# Debug-unit_rev01.net
KiCad netlist of a schematic drawn in EAGLE
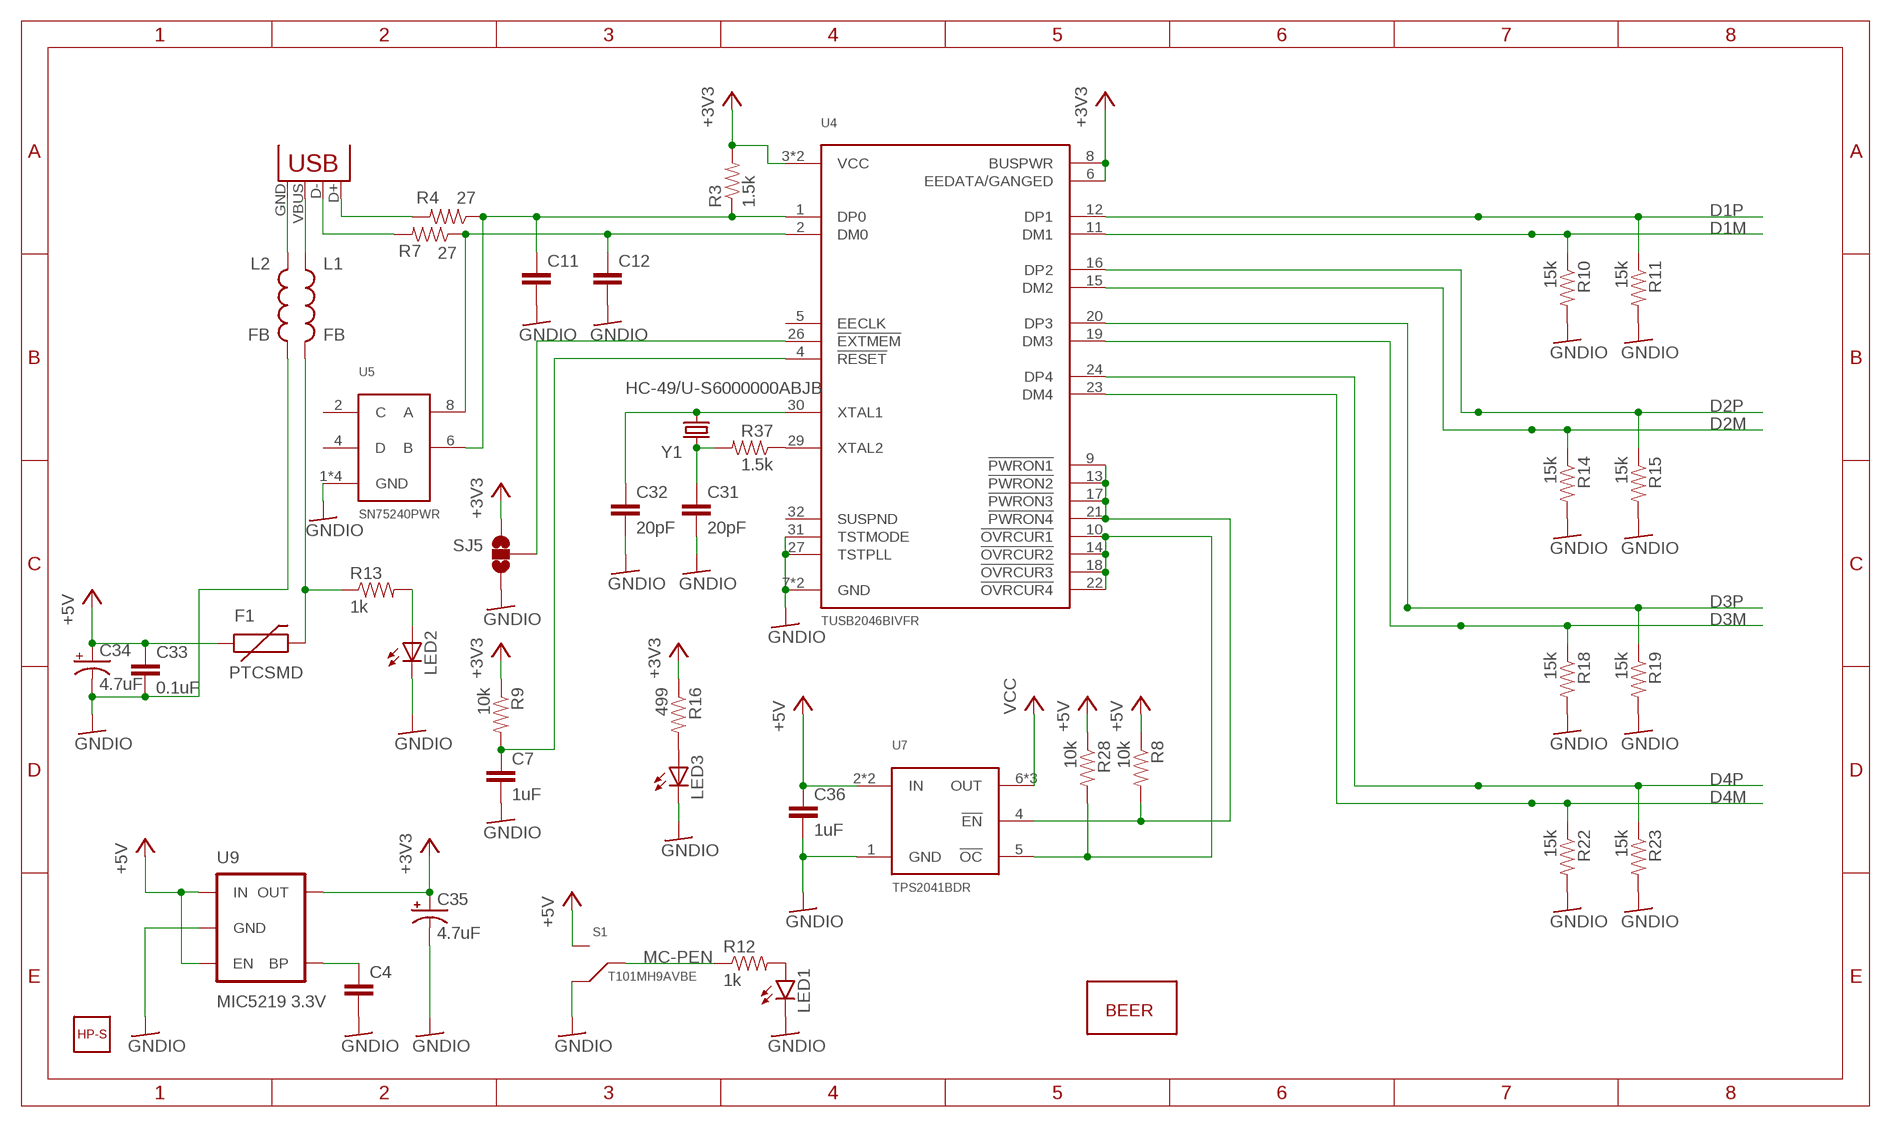
[diagram p0: schematic, sheet 1]
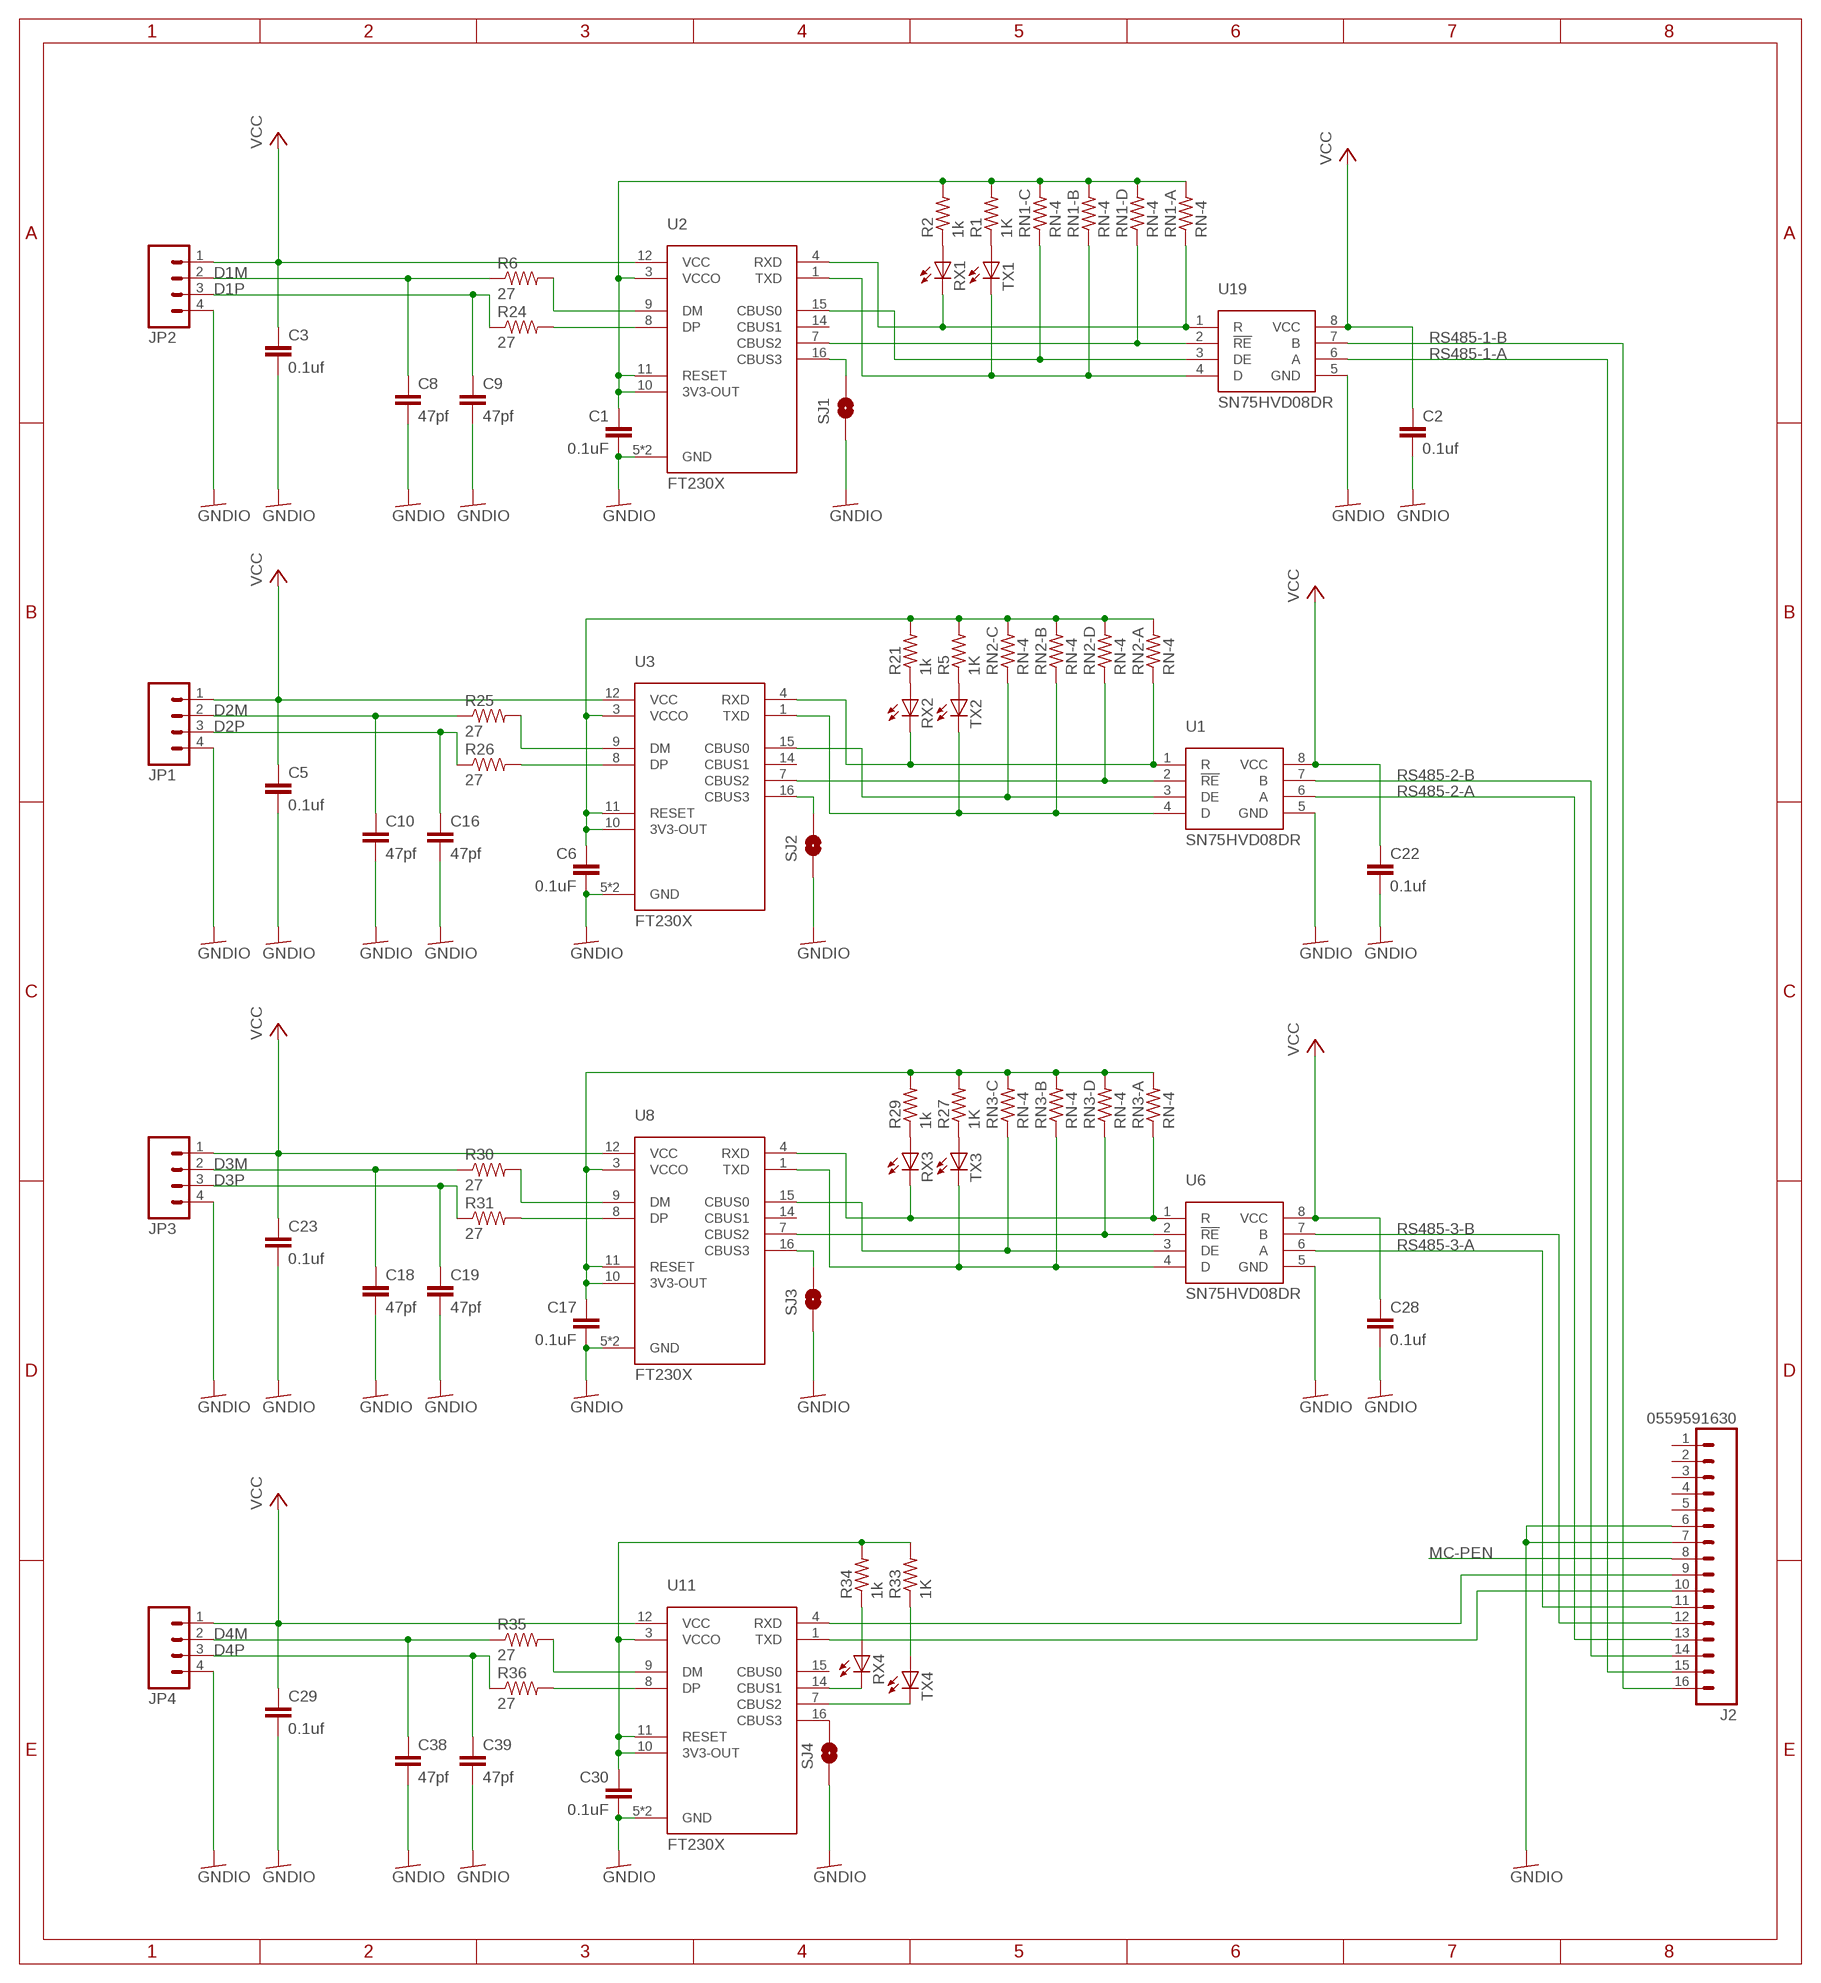
[diagram p1: schematic, sheet 2]

(export (version "E")
  (design (tool "Eeschema 10.0.6"))
  (components
    (comp (ref "C4")
      (value "CAP0805")
      (footprint "eagle-import:0805")
      (libsource (lib "eagle-import") (part "SparkFun-Passives_CAP0805"))
    )
    (comp (ref "C7")
      (value "1uF")
      (footprint "eagle-import:0805")
      (libsource (lib "eagle-import") (part "SparkFun-Passives_CAP0805"))
    )
    (comp (ref "C11")
      (value "CAP0805")
      (footprint "eagle-import:0805")
      (libsource (lib "eagle-import") (part "SparkFun-Passives_CAP0805"))
    )
    (comp (ref "C12")
      (value "CAP0805")
      (footprint "eagle-import:0805")
      (libsource (lib "eagle-import") (part "SparkFun-Passives_CAP0805"))
    )
    (comp (ref "C31")
      (value "20pF")
      (footprint "eagle-import:0805")
      (libsource (lib "eagle-import") (part "SparkFun-Passives_CAP0805"))
    )
    (comp (ref "C32")
      (value "20pF")
      (footprint "eagle-import:0805")
      (libsource (lib "eagle-import") (part "SparkFun-Passives_CAP0805"))
    )
    (comp (ref "C33")
      (value "0.1uF")
      (footprint "eagle-import:0805")
      (libsource (lib "eagle-import") (part "SparkFun-Passives_CAP0805"))
    )
    (comp (ref "C34")
      (value "4.7uF")
      (footprint "eagle-import:EIA3216")
      (libsource (lib "eagle-import") (part "CAP_POL1206"))
    )
    (comp (ref "C35")
      (value "4.7uF")
      (footprint "eagle-import:EIA3216")
      (libsource (lib "eagle-import") (part "CAP_POL1206"))
    )
    (comp (ref "C36")
      (value "1uF")
      (footprint "eagle-import:0805")
      (libsource (lib "eagle-import") (part "SparkFun-Passives_CAP0805"))
    )
    (comp (ref "F1")
      (value "PTCSMD")
      (footprint "eagle-import:PTC-1206")
      (libsource (lib "eagle-import") (part "PTCSMD"))
    )
    (comp (ref "JP9")
      (value "USB-B")
      (footprint "eagle-import:USB-B-PTH")
      (libsource (lib "eagle-import") (part "USBPTH"))
    )
    (comp (ref "L1")
      (value "FB")
      (footprint "eagle-import:0805")
      (libsource (lib "eagle-import") (part "INDUCTOR0805"))
    )
    (comp (ref "L2")
      (value "FB")
      (footprint "eagle-import:0805")
      (libsource (lib "eagle-import") (part "INDUCTOR0805"))
    )
    (comp (ref "LED1")
      (value "LED-3MM-NO_SILK")
      (footprint "eagle-import:LED3MM-NS")
      (libsource (lib "eagle-import") (part "LED-3MM-NO_SILK"))
    )
    (comp (ref "LED2")
      (value "LEDCHIP-LED0805")
      (footprint "eagle-import:CHIP-LED0805")
      (libsource (lib "eagle-import") (part "LEDCHIP-LED0805"))
    )
    (comp (ref "LED3")
      (value "LEDCHIP-LED0805")
      (footprint "eagle-import:CHIP-LED0805")
      (libsource (lib "eagle-import") (part "LEDCHIP-LED0805"))
    )
    (comp (ref "R3")
      (value "1.5k")
      (footprint "eagle-import:0805")
      (libsource (lib "eagle-import") (part "RESISTOR0805-RES"))
    )
    (comp (ref "R4")
      (value "27")
      (footprint "eagle-import:0805")
      (libsource (lib "eagle-import") (part "RESISTOR0805-RES"))
    )
    (comp (ref "R7")
      (value "27")
      (footprint "eagle-import:0805")
      (libsource (lib "eagle-import") (part "RESISTOR0805-RES"))
    )
    (comp (ref "R8")
      (value "10k")
      (footprint "eagle-import:0805")
      (libsource (lib "eagle-import") (part "RESISTOR0805-RES"))
    )
    (comp (ref "R9")
      (value "10k")
      (footprint "eagle-import:0805")
      (libsource (lib "eagle-import") (part "RESISTOR0805-RES"))
    )
    (comp (ref "R10")
      (value "15k")
      (footprint "eagle-import:0805")
      (libsource (lib "eagle-import") (part "RESISTOR0805-RES"))
    )
    (comp (ref "R11")
      (value "15k")
      (footprint "eagle-import:0805")
      (libsource (lib "eagle-import") (part "RESISTOR0805-RES"))
    )
    (comp (ref "R12")
      (value "1k")
      (footprint "eagle-import:0805")
      (libsource (lib "eagle-import") (part "RESISTOR0805-RES"))
    )
    (comp (ref "R13")
      (value "1k")
      (footprint "eagle-import:0805")
      (libsource (lib "eagle-import") (part "RESISTOR0805-RES"))
    )
    (comp (ref "R14")
      (value "15k")
      (footprint "eagle-import:0805")
      (libsource (lib "eagle-import") (part "RESISTOR0805-RES"))
    )
    (comp (ref "R15")
      (value "15k")
      (footprint "eagle-import:0805")
      (libsource (lib "eagle-import") (part "RESISTOR0805-RES"))
    )
    (comp (ref "R16")
      (value "499")
      (footprint "eagle-import:0805")
      (libsource (lib "eagle-import") (part "RESISTOR0805-RES"))
    )
    (comp (ref "R18")
      (value "15k")
      (footprint "eagle-import:0805")
      (libsource (lib "eagle-import") (part "RESISTOR0805-RES"))
    )
    (comp (ref "R19")
      (value "15k")
      (footprint "eagle-import:0805")
      (libsource (lib "eagle-import") (part "RESISTOR0805-RES"))
    )
    (comp (ref "R22")
      (value "15k")
      (footprint "eagle-import:0805")
      (libsource (lib "eagle-import") (part "RESISTOR0805-RES"))
    )
    (comp (ref "R23")
      (value "15k")
      (footprint "eagle-import:0805")
      (libsource (lib "eagle-import") (part "RESISTOR0805-RES"))
    )
    (comp (ref "R28")
      (value "10k")
      (footprint "eagle-import:0805")
      (libsource (lib "eagle-import") (part "RESISTOR0805-RES"))
    )
    (comp (ref "R37")
      (value "1.5k")
      (footprint "eagle-import:0805")
      (libsource (lib "eagle-import") (part "RESISTOR0805-RES"))
    )
    (comp (ref "S1")
      (value "T101MH9AVBE")
      (footprint "eagle-import:T101MH9AVBE")
      (libsource (lib "eagle-import") (part "T101MH9AVBE"))
    )
    (comp (ref "SJ5")
      (value "JUMPER-PAD-3-NOFULL_BOX_SILK")
      (footprint "eagle-import:PAD-JUMPER-3-NO_YES_SILK_FULL_BOX")
      (libsource (lib "eagle-import") (part "JUMPER-PAD-3-NOFULL_BOX_SILK"))
    )
    (comp (ref "U$1")
      (value "HP-3651-B")
      (footprint "eagle-import:HP-3651-B")
      (libsource (lib "eagle-import") (part "HP-3651-B"))
    )
    (comp (ref "U$3")
      (value "BEERS")
      (footprint "eagle-import:B-S")
      (libsource (lib "eagle-import") (part "BEERS"))
    )
    (comp (ref "U4")
      (value "TUSB2046BIVFR")
      (footprint "eagle-import:LQFP-32")
      (libsource (lib "eagle-import") (part "TUSB2046BIVFR"))
    )
    (comp (ref "U5")
      (value "SN75240PWR")
      (footprint "eagle-import:TSSOP-8")
      (libsource (lib "eagle-import") (part "SN75240PWR"))
    )
    (comp (ref "U7")
      (value "TPS2041BDR")
      (footprint "eagle-import:SO-8")
      (libsource (lib "eagle-import") (part "TPS2041BDR"))
    )
    (comp (ref "U9")
      (value "MIC5219 3.3V")
      (footprint "eagle-import:SOT23-5")
      (libsource (lib "eagle-import") (part "V_REG_MIC52193.3V"))
    )
    (comp (ref "Y1")
      (value "HC-49/U-S6000000ABJB")
      (footprint "eagle-import:HC49US")
      (libsource (lib "eagle-import") (part "CRYSTALHC49US"))
    )
    (comp (ref "C1")
      (value "0.1uF")
      (footprint "eagle-import:0805")
      (libsource (lib "eagle-import") (part "CAP0805"))
    )
    (comp (ref "C2")
      (value "0.1uf")
      (footprint "eagle-import:0805")
      (libsource (lib "eagle-import") (part "CAP0805"))
    )
    (comp (ref "C3")
      (value "0.1uf")
      (footprint "eagle-import:0805")
      (libsource (lib "eagle-import") (part "CAP0805"))
    )
    (comp (ref "C5")
      (value "0.1uf")
      (footprint "eagle-import:0805")
      (libsource (lib "eagle-import") (part "CAP0805"))
    )
    (comp (ref "C6")
      (value "0.1uF")
      (footprint "eagle-import:0805")
      (libsource (lib "eagle-import") (part "CAP0805"))
    )
    (comp (ref "C8")
      (value "47pf")
      (footprint "eagle-import:0805")
      (libsource (lib "eagle-import") (part "CAP0805"))
    )
    (comp (ref "C9")
      (value "47pf")
      (footprint "eagle-import:0805")
      (libsource (lib "eagle-import") (part "CAP0805"))
    )
    (comp (ref "C10")
      (value "47pf")
      (footprint "eagle-import:0805")
      (libsource (lib "eagle-import") (part "CAP0805"))
    )
    (comp (ref "C16")
      (value "47pf")
      (footprint "eagle-import:0805")
      (libsource (lib "eagle-import") (part "CAP0805"))
    )
    (comp (ref "C17")
      (value "0.1uF")
      (footprint "eagle-import:0805")
      (libsource (lib "eagle-import") (part "CAP0805"))
    )
    (comp (ref "C18")
      (value "47pf")
      (footprint "eagle-import:0805")
      (libsource (lib "eagle-import") (part "CAP0805"))
    )
    (comp (ref "C19")
      (value "47pf")
      (footprint "eagle-import:0805")
      (libsource (lib "eagle-import") (part "CAP0805"))
    )
    (comp (ref "C22")
      (value "0.1uf")
      (footprint "eagle-import:0805")
      (libsource (lib "eagle-import") (part "CAP0805"))
    )
    (comp (ref "C23")
      (value "0.1uf")
      (footprint "eagle-import:0805")
      (libsource (lib "eagle-import") (part "CAP0805"))
    )
    (comp (ref "C28")
      (value "0.1uf")
      (footprint "eagle-import:0805")
      (libsource (lib "eagle-import") (part "CAP0805"))
    )
    (comp (ref "C29")
      (value "0.1uf")
      (footprint "eagle-import:0805")
      (libsource (lib "eagle-import") (part "CAP0805"))
    )
    (comp (ref "C30")
      (value "0.1uF")
      (footprint "eagle-import:0805")
      (libsource (lib "eagle-import") (part "CAP0805"))
    )
    (comp (ref "C38")
      (value "47pf")
      (footprint "eagle-import:0805")
      (libsource (lib "eagle-import") (part "CAP0805"))
    )
    (comp (ref "C39")
      (value "47pf")
      (footprint "eagle-import:0805")
      (libsource (lib "eagle-import") (part "CAP0805"))
    )
    (comp (ref "J2")
      (value "0559591630")
      (footprint "eagle-import:0559591630")
      (libsource (lib "eagle-import") (part "0559591630"))
    )
    (comp (ref "JP1")
      (value "M04POLAR_LOCK")
      (footprint "eagle-import:MOLEX-1X4_LOCK")
      (libsource (lib "eagle-import") (part "M04POLAR_LOCK"))
    )
    (comp (ref "JP2")
      (value "M04POLAR_LOCK")
      (footprint "eagle-import:MOLEX-1X4_LOCK")
      (libsource (lib "eagle-import") (part "M04POLAR_LOCK"))
    )
    (comp (ref "JP3")
      (value "M04POLAR_LOCK")
      (footprint "eagle-import:MOLEX-1X4_LOCK")
      (libsource (lib "eagle-import") (part "M04POLAR_LOCK"))
    )
    (comp (ref "JP4")
      (value "M04POLAR_LOCK")
      (footprint "eagle-import:MOLEX-1X4_LOCK")
      (libsource (lib "eagle-import") (part "M04POLAR_LOCK"))
    )
    (comp (ref "R1")
      (value "1K")
      (footprint "eagle-import:R0805")
      (libsource (lib "eagle-import") (part "R-US_R0805"))
    )
    (comp (ref "R2")
      (value "1k")
      (footprint "eagle-import:R0805")
      (libsource (lib "eagle-import") (part "R-US_R0805"))
    )
    (comp (ref "R5")
      (value "1K")
      (footprint "eagle-import:R0805")
      (libsource (lib "eagle-import") (part "R-US_R0805"))
    )
    (comp (ref "R6")
      (value "27")
      (footprint "eagle-import:0805")
      (libsource (lib "eagle-import") (part "RESISTOR0805-RES"))
    )
    (comp (ref "R21")
      (value "1k")
      (footprint "eagle-import:R0805")
      (libsource (lib "eagle-import") (part "R-US_R0805"))
    )
    (comp (ref "R24")
      (value "27")
      (footprint "eagle-import:0805")
      (libsource (lib "eagle-import") (part "RESISTOR0805-RES"))
    )
    (comp (ref "R25")
      (value "27")
      (footprint "eagle-import:0805")
      (libsource (lib "eagle-import") (part "RESISTOR0805-RES"))
    )
    (comp (ref "R26")
      (value "27")
      (footprint "eagle-import:0805")
      (libsource (lib "eagle-import") (part "RESISTOR0805-RES"))
    )
    (comp (ref "R27")
      (value "1K")
      (footprint "eagle-import:R0805")
      (libsource (lib "eagle-import") (part "R-US_R0805"))
    )
    (comp (ref "R29")
      (value "1k")
      (footprint "eagle-import:R0805")
      (libsource (lib "eagle-import") (part "R-US_R0805"))
    )
    (comp (ref "R30")
      (value "27")
      (footprint "eagle-import:0805")
      (libsource (lib "eagle-import") (part "RESISTOR0805-RES"))
    )
    (comp (ref "R31")
      (value "27")
      (footprint "eagle-import:0805")
      (libsource (lib "eagle-import") (part "RESISTOR0805-RES"))
    )
    (comp (ref "R33")
      (value "1K")
      (footprint "eagle-import:R0805")
      (libsource (lib "eagle-import") (part "R-US_R0805"))
    )
    (comp (ref "R34")
      (value "1k")
      (footprint "eagle-import:R0805")
      (libsource (lib "eagle-import") (part "R-US_R0805"))
    )
    (comp (ref "R35")
      (value "27")
      (footprint "eagle-import:0805")
      (libsource (lib "eagle-import") (part "RESISTOR0805-RES"))
    )
    (comp (ref "R36")
      (value "27")
      (footprint "eagle-import:0805")
      (libsource (lib "eagle-import") (part "RESISTOR0805-RES"))
    )
    (comp (ref "RN1")
      (value "RN-4")
      (footprint "eagle-import:CRA06S")
      (libsource (lib "eagle-import") (part "RN-4"))
    )
    (comp (ref "RN2")
      (value "RN-4")
      (footprint "eagle-import:CRA06S")
      (libsource (lib "eagle-import") (part "RN-4"))
    )
    (comp (ref "RN3")
      (value "RN-4")
      (footprint "eagle-import:CRA06S")
      (libsource (lib "eagle-import") (part "RN-4"))
    )
    (comp (ref "RX1")
      (value "LEDCHIPLED_0805")
      (footprint "eagle-import:CHIPLED_0805")
      (libsource (lib "eagle-import") (part "LEDCHIPLED_0805"))
    )
    (comp (ref "RX2")
      (value "LEDCHIPLED_0805")
      (footprint "eagle-import:CHIPLED_0805")
      (libsource (lib "eagle-import") (part "LEDCHIPLED_0805"))
    )
    (comp (ref "RX3")
      (value "LEDCHIPLED_0805")
      (footprint "eagle-import:CHIPLED_0805")
      (libsource (lib "eagle-import") (part "LEDCHIPLED_0805"))
    )
    (comp (ref "RX4")
      (value "LEDCHIPLED_0805")
      (footprint "eagle-import:CHIPLED_0805")
      (libsource (lib "eagle-import") (part "LEDCHIPLED_0805"))
    )
    (comp (ref "SJ1")
      (value "JUMPER-PAD-2-NOYES_SILK")
      (footprint "eagle-import:PAD-JUMPER-2-NO_YES_SILK")
      (libsource (lib "eagle-import") (part "JUMPER-PAD-2-NOYES_SILK"))
    )
    (comp (ref "SJ2")
      (value "JUMPER-PAD-2-NOYES_SILK")
      (footprint "eagle-import:PAD-JUMPER-2-NO_YES_SILK")
      (libsource (lib "eagle-import") (part "JUMPER-PAD-2-NOYES_SILK"))
    )
    (comp (ref "SJ3")
      (value "JUMPER-PAD-2-NOYES_SILK")
      (footprint "eagle-import:PAD-JUMPER-2-NO_YES_SILK")
      (libsource (lib "eagle-import") (part "JUMPER-PAD-2-NOYES_SILK"))
    )
    (comp (ref "SJ4")
      (value "JUMPER-PAD-2-NOYES_SILK")
      (footprint "eagle-import:PAD-JUMPER-2-NO_YES_SILK")
      (libsource (lib "eagle-import") (part "JUMPER-PAD-2-NOYES_SILK"))
    )
    (comp (ref "TX1")
      (value "LEDCHIPLED_0805")
      (footprint "eagle-import:CHIPLED_0805")
      (libsource (lib "eagle-import") (part "LEDCHIPLED_0805"))
    )
    (comp (ref "TX2")
      (value "LEDCHIPLED_0805")
      (footprint "eagle-import:CHIPLED_0805")
      (libsource (lib "eagle-import") (part "LEDCHIPLED_0805"))
    )
    (comp (ref "TX3")
      (value "LEDCHIPLED_0805")
      (footprint "eagle-import:CHIPLED_0805")
      (libsource (lib "eagle-import") (part "LEDCHIPLED_0805"))
    )
    (comp (ref "TX4")
      (value "LEDCHIPLED_0805")
      (footprint "eagle-import:CHIPLED_0805")
      (libsource (lib "eagle-import") (part "LEDCHIPLED_0805"))
    )
    (comp (ref "U1")
      (value "SN75HVD08DR")
      (footprint "eagle-import:SO-8")
      (libsource (lib "eagle-import") (part "SN75HVD08DR"))
    )
    (comp (ref "U2")
      (value "FT230X")
      (footprint "eagle-import:SSOP-16")
      (libsource (lib "eagle-import") (part "FT230X"))
    )
    (comp (ref "U3")
      (value "FT230X")
      (footprint "eagle-import:SSOP-16")
      (libsource (lib "eagle-import") (part "FT230X"))
    )
    (comp (ref "U6")
      (value "SN75HVD08DR")
      (footprint "eagle-import:SO-8")
      (libsource (lib "eagle-import") (part "SN75HVD08DR"))
    )
    (comp (ref "U8")
      (value "FT230X")
      (footprint "eagle-import:SSOP-16")
      (libsource (lib "eagle-import") (part "FT230X"))
    )
    (comp (ref "U11")
      (value "FT230X")
      (footprint "eagle-import:SSOP-16")
      (libsource (lib "eagle-import") (part "FT230X"))
    )
    (comp (ref "U19")
      (value "SN75HVD08DR")
      (footprint "eagle-import:SO-8")
      (libsource (lib "eagle-import") (part "SN75HVD08DR"))
    )
  )
  (nets
    (net (code "1") (name "+3V3") (class "Default")
      (node (ref "C35") (pin "A") (pinfunction "+_A") (pintype "passive"))
      (node (ref "R16") (pin "1") (pinfunction "1_1") (pintype "passive"))
      (node (ref "R3") (pin "2") (pinfunction "2_2") (pintype "passive"))
      (node (ref "R9") (pin "1") (pinfunction "1_1") (pintype "passive"))
      (node (ref "SJ5") (pin "1") (pinfunction "1_1") (pintype "passive"))
      (node (ref "U4") (pin "25") (pinfunction "VCC_25") (pintype "bidirectional"))
      (node (ref "U4") (pin "3") (pinfunction "VCC_3") (pintype "bidirectional"))
      (node (ref "U4") (pin "6") (pinfunction "EEDATA/GANGED_6") (pintype "bidirectional"))
      (node (ref "U4") (pin "8") (pinfunction "BUSPWR_8") (pintype "bidirectional"))
      (node (ref "U9") (pin "5") (pinfunction "OUT_5") (pintype "passive"))
    )
    (net (code "2") (name "+5V") (class "Default")
      (node (ref "C33") (pin "1") (pinfunction "1_1") (pintype "passive"))
      (node (ref "C34") (pin "A") (pinfunction "+_A") (pintype "passive"))
      (node (ref "C36") (pin "1") (pinfunction "1_1") (pintype "passive"))
      (node (ref "F1") (pin "1") (pinfunction "1_1") (pintype "bidirectional"))
      (node (ref "R28") (pin "1") (pinfunction "1_1") (pintype "passive"))
      (node (ref "R8") (pin "1") (pinfunction "1_1") (pintype "passive"))
      (node (ref "S1") (pin "1") (pinfunction "NO_1") (pintype "bidirectional"))
      (node (ref "U7") (pin "2") (pinfunction "IN_2") (pintype "bidirectional"))
      (node (ref "U7") (pin "3") (pinfunction "IN_3") (pintype "bidirectional"))
      (node (ref "U9") (pin "1") (pinfunction "IN_1") (pintype "input"))
      (node (ref "U9") (pin "3") (pinfunction "EN_3") (pintype "input"))
    )
    (net (code "3") (name "D1M") (class "Default")
      (node (ref "C8") (pin "1") (pinfunction "1_1") (pintype "passive"))
      (node (ref "JP2") (pin "2") (pinfunction "2_2") (pintype "passive"))
      (node (ref "R10") (pin "1") (pinfunction "1_1") (pintype "passive"))
      (node (ref "R6") (pin "1") (pinfunction "1_1") (pintype "passive"))
      (node (ref "U4") (pin "11") (pinfunction "DM1_11") (pintype "bidirectional"))
    )
    (net (code "4") (name "D1P") (class "Default")
      (node (ref "C9") (pin "1") (pinfunction "1_1") (pintype "passive"))
      (node (ref "JP2") (pin "3") (pinfunction "3_3") (pintype "passive"))
      (node (ref "R11") (pin "1") (pinfunction "1_1") (pintype "passive"))
      (node (ref "R24") (pin "1") (pinfunction "1_1") (pintype "passive"))
      (node (ref "U4") (pin "12") (pinfunction "DP1_12") (pintype "bidirectional"))
    )
    (net (code "5") (name "D2M") (class "Default")
      (node (ref "C10") (pin "1") (pinfunction "1_1") (pintype "passive"))
      (node (ref "JP1") (pin "2") (pinfunction "2_2") (pintype "passive"))
      (node (ref "R14") (pin "1") (pinfunction "1_1") (pintype "passive"))
      (node (ref "R25") (pin "1") (pinfunction "1_1") (pintype "passive"))
      (node (ref "U4") (pin "15") (pinfunction "DM2_15") (pintype "bidirectional"))
    )
    (net (code "6") (name "D2P") (class "Default")
      (node (ref "C16") (pin "1") (pinfunction "1_1") (pintype "passive"))
      (node (ref "JP1") (pin "3") (pinfunction "3_3") (pintype "passive"))
      (node (ref "R15") (pin "1") (pinfunction "1_1") (pintype "passive"))
      (node (ref "R26") (pin "1") (pinfunction "1_1") (pintype "passive"))
      (node (ref "U4") (pin "16") (pinfunction "DP2_16") (pintype "bidirectional"))
    )
    (net (code "7") (name "D3M") (class "Default")
      (node (ref "C18") (pin "1") (pinfunction "1_1") (pintype "passive"))
      (node (ref "JP3") (pin "2") (pinfunction "2_2") (pintype "passive"))
      (node (ref "R18") (pin "1") (pinfunction "1_1") (pintype "passive"))
      (node (ref "R30") (pin "1") (pinfunction "1_1") (pintype "passive"))
      (node (ref "U4") (pin "19") (pinfunction "DM3_19") (pintype "bidirectional"))
    )
    (net (code "8") (name "D3P") (class "Default")
      (node (ref "C19") (pin "1") (pinfunction "1_1") (pintype "passive"))
      (node (ref "JP3") (pin "3") (pinfunction "3_3") (pintype "passive"))
      (node (ref "R19") (pin "1") (pinfunction "1_1") (pintype "passive"))
      (node (ref "R31") (pin "1") (pinfunction "1_1") (pintype "passive"))
      (node (ref "U4") (pin "20") (pinfunction "DP3_20") (pintype "bidirectional"))
    )
    (net (code "9") (name "D4M") (class "Default")
      (node (ref "C38") (pin "1") (pinfunction "1_1") (pintype "passive"))
      (node (ref "JP4") (pin "2") (pinfunction "2_2") (pintype "passive"))
      (node (ref "R22") (pin "1") (pinfunction "1_1") (pintype "passive"))
      (node (ref "R35") (pin "1") (pinfunction "1_1") (pintype "passive"))
      (node (ref "U4") (pin "23") (pinfunction "DM4_23") (pintype "bidirectional"))
    )
    (net (code "10") (name "D4P") (class "Default")
      (node (ref "C39") (pin "1") (pinfunction "1_1") (pintype "passive"))
      (node (ref "JP4") (pin "3") (pinfunction "3_3") (pintype "passive"))
      (node (ref "R23") (pin "1") (pinfunction "1_1") (pintype "passive"))
      (node (ref "R36") (pin "1") (pinfunction "1_1") (pintype "passive"))
      (node (ref "U4") (pin "24") (pinfunction "DP4_24") (pintype "bidirectional"))
    )
    (net (code "11") (name "GNDIO") (class "Default")
      (node (ref "C1") (pin "2") (pinfunction "2_2") (pintype "passive"))
      (node (ref "C10") (pin "2") (pinfunction "2_2") (pintype "passive"))
      (node (ref "C11") (pin "2") (pinfunction "2_2") (pintype "passive"))
      (node (ref "C12") (pin "2") (pinfunction "2_2") (pintype "passive"))
      (node (ref "C16") (pin "2") (pinfunction "2_2") (pintype "passive"))
      (node (ref "C17") (pin "2") (pinfunction "2_2") (pintype "passive"))
      (node (ref "C18") (pin "2") (pinfunction "2_2") (pintype "passive"))
      (node (ref "C19") (pin "2") (pinfunction "2_2") (pintype "passive"))
      (node (ref "C2") (pin "2") (pinfunction "2_2") (pintype "passive"))
      (node (ref "C22") (pin "2") (pinfunction "2_2") (pintype "passive"))
      (node (ref "C23") (pin "2") (pinfunction "2_2") (pintype "passive"))
      (node (ref "C28") (pin "2") (pinfunction "2_2") (pintype "passive"))
      (node (ref "C29") (pin "2") (pinfunction "2_2") (pintype "passive"))
      (node (ref "C3") (pin "2") (pinfunction "2_2") (pintype "passive"))
      (node (ref "C30") (pin "2") (pinfunction "2_2") (pintype "passive"))
      (node (ref "C31") (pin "2") (pinfunction "2_2") (pintype "passive"))
      (node (ref "C32") (pin "2") (pinfunction "2_2") (pintype "passive"))
      (node (ref "C33") (pin "2") (pinfunction "2_2") (pintype "passive"))
      (node (ref "C34") (pin "C") (pinfunction "-_C") (pintype "passive"))
      (node (ref "C35") (pin "C") (pinfunction "-_C") (pintype "passive"))
      (node (ref "C36") (pin "2") (pinfunction "2_2") (pintype "passive"))
      (node (ref "C38") (pin "2") (pinfunction "2_2") (pintype "passive"))
      (node (ref "C39") (pin "2") (pinfunction "2_2") (pintype "passive"))
      (node (ref "C4") (pin "2") (pinfunction "2_2") (pintype "passive"))
      (node (ref "C5") (pin "2") (pinfunction "2_2") (pintype "passive"))
      (node (ref "C6") (pin "2") (pinfunction "2_2") (pintype "passive"))
      (node (ref "C7") (pin "2") (pinfunction "2_2") (pintype "passive"))
      (node (ref "C8") (pin "2") (pinfunction "2_2") (pintype "passive"))
      (node (ref "C9") (pin "2") (pinfunction "2_2") (pintype "passive"))
      (node (ref "J2") (pin "6") (pinfunction "6_6") (pintype "passive"))
      (node (ref "J2") (pin "7") (pinfunction "7_7") (pintype "passive"))
      (node (ref "JP1") (pin "4") (pinfunction "4_4") (pintype "passive"))
      (node (ref "JP2") (pin "4") (pinfunction "4_4") (pintype "passive"))
      (node (ref "JP3") (pin "4") (pinfunction "4_4") (pintype "passive"))
      (node (ref "JP4") (pin "4") (pinfunction "4_4") (pintype "passive"))
      (node (ref "L2") (pin "2") (pinfunction "2_2") (pintype "passive"))
      (node (ref "LED1") (pin "K") (pinfunction "C_K") (pintype "passive"))
      (node (ref "LED2") (pin "C") (pinfunction "C_C") (pintype "passive"))
      (node (ref "LED3") (pin "C") (pinfunction "C_C") (pintype "passive"))
      (node (ref "R10") (pin "2") (pinfunction "2_2") (pintype "passive"))
      (node (ref "R11") (pin "2") (pinfunction "2_2") (pintype "passive"))
      (node (ref "R14") (pin "2") (pinfunction "2_2") (pintype "passive"))
      (node (ref "R15") (pin "2") (pinfunction "2_2") (pintype "passive"))
      (node (ref "R18") (pin "2") (pinfunction "2_2") (pintype "passive"))
      (node (ref "R19") (pin "2") (pinfunction "2_2") (pintype "passive"))
      (node (ref "R22") (pin "2") (pinfunction "2_2") (pintype "passive"))
      (node (ref "R23") (pin "2") (pinfunction "2_2") (pintype "passive"))
      (node (ref "S1") (pin "3") (pinfunction "NC_3") (pintype "bidirectional"))
      (node (ref "SJ1") (pin "1") (pinfunction "1_1") (pintype "passive"))
      (node (ref "SJ2") (pin "1") (pinfunction "1_1") (pintype "passive"))
      (node (ref "SJ3") (pin "1") (pinfunction "1_1") (pintype "passive"))
      (node (ref "SJ4") (pin "1") (pinfunction "1_1") (pintype "passive"))
      (node (ref "SJ5") (pin "3") (pinfunction "3_3") (pintype "passive"))
      (node (ref "U1") (pin "5") (pinfunction "GND_5") (pintype "bidirectional"))
      (node (ref "U11") (pin "13") (pinfunction "GND_13") (pintype "bidirectional"))
      (node (ref "U11") (pin "5") (pinfunction "GND_5") (pintype "bidirectional"))
      (node (ref "U19") (pin "5") (pinfunction "GND_5") (pintype "bidirectional"))
      (node (ref "U2") (pin "13") (pinfunction "GND_13") (pintype "bidirectional"))
      (node (ref "U2") (pin "5") (pinfunction "GND_5") (pintype "bidirectional"))
      (node (ref "U3") (pin "13") (pinfunction "GND_13") (pintype "bidirectional"))
      (node (ref "U3") (pin "5") (pinfunction "GND_5") (pintype "bidirectional"))
      (node (ref "U4") (pin "27") (pinfunction "TSTPLL_27") (pintype "bidirectional"))
      (node (ref "U4") (pin "28") (pinfunction "GND_28") (pintype "bidirectional"))
      (node (ref "U4") (pin "31") (pinfunction "TSTMODE_31") (pintype "bidirectional"))
      (node (ref "U4") (pin "7") (pinfunction "GND_7") (pintype "bidirectional"))
      (node (ref "U5") (pin "1") (pinfunction "GND_1") (pintype "bidirectional"))
      (node (ref "U5") (pin "3") (pinfunction "GND_3") (pintype "bidirectional"))
      (node (ref "U5") (pin "5") (pinfunction "GND_5") (pintype "bidirectional"))
      (node (ref "U5") (pin "7") (pinfunction "GND_7") (pintype "bidirectional"))
      (node (ref "U6") (pin "5") (pinfunction "GND_5") (pintype "bidirectional"))
      (node (ref "U7") (pin "1") (pinfunction "GND_1") (pintype "bidirectional"))
      (node (ref "U8") (pin "13") (pinfunction "GND_13") (pintype "bidirectional"))
      (node (ref "U8") (pin "5") (pinfunction "GND_5") (pintype "bidirectional"))
      (node (ref "U9") (pin "2") (pinfunction "GND_2") (pintype "input"))
    )
    (net (code "12") (name "MC-PEN") (class "Default")
      (node (ref "J2") (pin "8") (pinfunction "8_8") (pintype "passive"))
      (node (ref "R12") (pin "1") (pinfunction "1_1") (pintype "passive"))
      (node (ref "S1") (pin "2") (pinfunction "C_2") (pintype "bidirectional"))
    )
    (net (code "13") (name "Net-(C31-Pad1)") (class "Default")
      (node (ref "C31") (pin "1") (pinfunction "1_1") (pintype "passive"))
      (node (ref "R37") (pin "2") (pinfunction "2_2") (pintype "passive"))
      (node (ref "Y1") (pin "2") (pinfunction "2_2") (pintype "passive"))
    )
    (net (code "14") (name "Net-(F1-Pad2)") (class "Default")
      (node (ref "F1") (pin "2") (pinfunction "2_2") (pintype "bidirectional"))
      (node (ref "L1") (pin "2") (pinfunction "2_2") (pintype "passive"))
      (node (ref "R13") (pin "1") (pinfunction "1_1") (pintype "passive"))
    )
    (net (code "15") (name "Net-(JP9-PadD+)") (class "Default")
      (node (ref "JP9") (pin "D+") (pinfunction "D+_D+") (pintype "bidirectional"))
      (node (ref "R4") (pin "2") (pinfunction "2_2") (pintype "passive"))
    )
    (net (code "16") (name "Net-(JP9-PadD-)") (class "Default")
      (node (ref "JP9") (pin "D-") (pinfunction "D-_D-") (pintype "bidirectional"))
      (node (ref "R7") (pin "2") (pinfunction "2_2") (pintype "passive"))
    )
    (net (code "17") (name "Net-(JP9-PadGND)") (class "Default")
      (node (ref "JP9") (pin "GND") (pinfunction "GND_GND") (pintype "bidirectional"))
      (node (ref "L2") (pin "1") (pinfunction "1_1") (pintype "passive"))
    )
    (net (code "18") (name "Net-(JP9-PadVBUS)") (class "Default")
      (node (ref "JP9") (pin "VBUS") (pinfunction "VBUS_VBUS") (pintype "bidirectional"))
      (node (ref "L1") (pin "1") (pinfunction "1_1") (pintype "passive"))
    )
    (net (code "19") (name "Net-(LED1-PadA)") (class "Default")
      (node (ref "LED1") (pin "A") (pinfunction "A_A") (pintype "passive"))
      (node (ref "R12") (pin "2") (pinfunction "2_2") (pintype "passive"))
    )
    (net (code "20") (name "Net-(LED2-PadA)") (class "Default")
      (node (ref "LED2") (pin "A") (pinfunction "A_A") (pintype "passive"))
      (node (ref "R13") (pin "2") (pinfunction "2_2") (pintype "passive"))
    )
    (net (code "21") (name "Net-(LED3-PadA)") (class "Default")
      (node (ref "LED3") (pin "A") (pinfunction "A_A") (pintype "passive"))
      (node (ref "R16") (pin "2") (pinfunction "2_2") (pintype "passive"))
    )
    (net (code "22") (name "Net-(R1-Pad1)") (class "Default")
      (node (ref "R1") (pin "1") (pinfunction "1_1") (pintype "passive"))
      (node (ref "TX1") (pin "A") (pinfunction "A_A") (pintype "passive"))
    )
    (net (code "23") (name "Net-(R2-Pad1)") (class "Default")
      (node (ref "R2") (pin "1") (pinfunction "1_1") (pintype "passive"))
      (node (ref "RX1") (pin "A") (pinfunction "A_A") (pintype "passive"))
    )
    (net (code "24") (name "Net-(R5-Pad1)") (class "Default")
      (node (ref "R5") (pin "1") (pinfunction "1_1") (pintype "passive"))
      (node (ref "TX2") (pin "A") (pinfunction "A_A") (pintype "passive"))
    )
    (net (code "25") (name "Net-(R21-Pad1)") (class "Default")
      (node (ref "R21") (pin "1") (pinfunction "1_1") (pintype "passive"))
      (node (ref "RX2") (pin "A") (pinfunction "A_A") (pintype "passive"))
    )
    (net (code "26") (name "Net-(R27-Pad1)") (class "Default")
      (node (ref "R27") (pin "1") (pinfunction "1_1") (pintype "passive"))
      (node (ref "TX3") (pin "A") (pinfunction "A_A") (pintype "passive"))
    )
    (net (code "27") (name "Net-(R29-Pad1)") (class "Default")
      (node (ref "R29") (pin "1") (pinfunction "1_1") (pintype "passive"))
      (node (ref "RX3") (pin "A") (pinfunction "A_A") (pintype "passive"))
    )
    (net (code "28") (name "Net-(R33-Pad1)") (class "Default")
      (node (ref "R33") (pin "1") (pinfunction "1_1") (pintype "passive"))
      (node (ref "TX4") (pin "A") (pinfunction "A_A") (pintype "passive"))
    )
    (net (code "29") (name "Net-(R34-Pad1)") (class "Default")
      (node (ref "R34") (pin "1") (pinfunction "1_1") (pintype "passive"))
      (node (ref "RX4") (pin "A") (pinfunction "A_A") (pintype "passive"))
    )
    (net (code "30") (name "Net-(RN1A-2)") (class "Default")
      (node (ref "C1") (pin "1") (pinfunction "1_1") (pintype "passive"))
      (node (ref "R1") (pin "2") (pinfunction "2_2") (pintype "passive"))
      (node (ref "R2") (pin "2") (pinfunction "2_2") (pintype "passive"))
      (node (ref "RN1") (pin "5") (pinfunction "2_5") (pintype "passive"))
      (node (ref "RN1") (pin "6") (pinfunction "2_6") (pintype "passive"))
      (node (ref "RN1") (pin "7") (pinfunction "2_7") (pintype "passive"))
      (node (ref "RN1") (pin "8") (pinfunction "2_8") (pintype "passive"))
      (node (ref "U2") (pin "10") (pinfunction "3V3-OUT_10") (pintype "bidirectional"))
      (node (ref "U2") (pin "11") (pinfunction "RESET_11") (pintype "bidirectional"))
      (node (ref "U2") (pin "3") (pinfunction "VCCO_3") (pintype "bidirectional"))
    )
    (net (code "31") (name "Net-(RN1B-1)") (class "Default")
      (node (ref "RN1") (pin "2") (pinfunction "1_2") (pintype "passive"))
      (node (ref "TX1") (pin "C") (pinfunction "C_C") (pintype "passive"))
      (node (ref "U19") (pin "4") (pinfunction "D_4") (pintype "bidirectional"))
      (node (ref "U2") (pin "1") (pinfunction "TXD_1") (pintype "bidirectional"))
    )
    (net (code "32") (name "Net-(RN1C-1)") (class "Default")
      (node (ref "RN1") (pin "3") (pinfunction "1_3") (pintype "passive"))
      (node (ref "U19") (pin "3") (pinfunction "DE_3") (pintype "bidirectional"))
      (node (ref "U2") (pin "15") (pinfunction "CBUS0_15") (pintype "bidirectional"))
    )
    (net (code "33") (name "Net-(RN1D-1)") (class "Default")
      (node (ref "RN1") (pin "4") (pinfunction "1_4") (pintype "passive"))
      (node (ref "U19") (pin "2") (pinfunction "~{RE}_2") (pintype "bidirectional"))
      (node (ref "U2") (pin "7") (pinfunction "CBUS2_7") (pintype "bidirectional"))
    )
    (net (code "34") (name "Net-(RN2A-2)") (class "Default")
      (node (ref "C6") (pin "1") (pinfunction "1_1") (pintype "passive"))
      (node (ref "R21") (pin "2") (pinfunction "2_2") (pintype "passive"))
      (node (ref "R5") (pin "2") (pinfunction "2_2") (pintype "passive"))
      (node (ref "RN2") (pin "5") (pinfunction "2_5") (pintype "passive"))
      (node (ref "RN2") (pin "6") (pinfunction "2_6") (pintype "passive"))
      (node (ref "RN2") (pin "7") (pinfunction "2_7") (pintype "passive"))
      (node (ref "RN2") (pin "8") (pinfunction "2_8") (pintype "passive"))
      (node (ref "U3") (pin "10") (pinfunction "3V3-OUT_10") (pintype "bidirectional"))
      (node (ref "U3") (pin "11") (pinfunction "RESET_11") (pintype "bidirectional"))
      (node (ref "U3") (pin "3") (pinfunction "VCCO_3") (pintype "bidirectional"))
    )
    (net (code "35") (name "Net-(RN2B-1)") (class "Default")
      (node (ref "RN2") (pin "2") (pinfunction "1_2") (pintype "passive"))
      (node (ref "TX2") (pin "C") (pinfunction "C_C") (pintype "passive"))
      (node (ref "U1") (pin "4") (pinfunction "D_4") (pintype "bidirectional"))
      (node (ref "U3") (pin "1") (pinfunction "TXD_1") (pintype "bidirectional"))
    )
    (net (code "36") (name "Net-(RN2C-1)") (class "Default")
      (node (ref "RN2") (pin "3") (pinfunction "1_3") (pintype "passive"))
      (node (ref "U1") (pin "3") (pinfunction "DE_3") (pintype "bidirectional"))
      (node (ref "U3") (pin "15") (pinfunction "CBUS0_15") (pintype "bidirectional"))
    )
    (net (code "37") (name "Net-(RN2D-1)") (class "Default")
      (node (ref "RN2") (pin "4") (pinfunction "1_4") (pintype "passive"))
      (node (ref "U1") (pin "2") (pinfunction "~{RE}_2") (pintype "bidirectional"))
      (node (ref "U3") (pin "7") (pinfunction "CBUS2_7") (pintype "bidirectional"))
    )
    (net (code "38") (name "Net-(RN3A-2)") (class "Default")
      (node (ref "C17") (pin "1") (pinfunction "1_1") (pintype "passive"))
      (node (ref "R27") (pin "2") (pinfunction "2_2") (pintype "passive"))
      (node (ref "R29") (pin "2") (pinfunction "2_2") (pintype "passive"))
      (node (ref "RN3") (pin "5") (pinfunction "2_5") (pintype "passive"))
      (node (ref "RN3") (pin "6") (pinfunction "2_6") (pintype "passive"))
      (node (ref "RN3") (pin "7") (pinfunction "2_7") (pintype "passive"))
      (node (ref "RN3") (pin "8") (pinfunction "2_8") (pintype "passive"))
      (node (ref "U8") (pin "10") (pinfunction "3V3-OUT_10") (pintype "bidirectional"))
      (node (ref "U8") (pin "11") (pinfunction "RESET_11") (pintype "bidirectional"))
      (node (ref "U8") (pin "3") (pinfunction "VCCO_3") (pintype "bidirectional"))
    )
    (net (code "39") (name "Net-(RN3B-1)") (class "Default")
      (node (ref "RN3") (pin "2") (pinfunction "1_2") (pintype "passive"))
      (node (ref "TX3") (pin "C") (pinfunction "C_C") (pintype "passive"))
      (node (ref "U6") (pin "4") (pinfunction "D_4") (pintype "bidirectional"))
      (node (ref "U8") (pin "1") (pinfunction "TXD_1") (pintype "bidirectional"))
    )
    (net (code "40") (name "Net-(RN3C-1)") (class "Default")
      (node (ref "RN3") (pin "3") (pinfunction "1_3") (pintype "passive"))
      (node (ref "U6") (pin "3") (pinfunction "DE_3") (pintype "bidirectional"))
      (node (ref "U8") (pin "15") (pinfunction "CBUS0_15") (pintype "bidirectional"))
    )
    (net (code "41") (name "Net-(RN3D-1)") (class "Default")
      (node (ref "RN3") (pin "4") (pinfunction "1_4") (pintype "passive"))
      (node (ref "U6") (pin "2") (pinfunction "~{RE}_2") (pintype "bidirectional"))
      (node (ref "U8") (pin "7") (pinfunction "CBUS2_7") (pintype "bidirectional"))
    )
    (net (code "42") (name "Net-(U1-R)") (class "Default")
      (node (ref "RN2") (pin "1") (pinfunction "1_1") (pintype "passive"))
      (node (ref "RX2") (pin "C") (pinfunction "C_C") (pintype "passive"))
      (node (ref "U1") (pin "1") (pinfunction "R_1") (pintype "bidirectional"))
      (node (ref "U3") (pin "4") (pinfunction "RXD_4") (pintype "bidirectional"))
    )
    (net (code "43") (name "Net-(U2-CBUS3)") (class "Default")
      (node (ref "SJ1") (pin "2") (pinfunction "2_2") (pintype "passive"))
      (node (ref "U2") (pin "16") (pinfunction "CBUS3_16") (pintype "bidirectional"))
    )
    (net (code "44") (name "Net-(U2-DM)") (class "Default")
      (node (ref "R6") (pin "2") (pinfunction "2_2") (pintype "passive"))
      (node (ref "U2") (pin "9") (pinfunction "DM_9") (pintype "bidirectional"))
    )
    (net (code "45") (name "Net-(U2-DP)") (class "Default")
      (node (ref "R24") (pin "2") (pinfunction "2_2") (pintype "passive"))
      (node (ref "U2") (pin "8") (pinfunction "DP_8") (pintype "bidirectional"))
    )
    (net (code "46") (name "Net-(U3-CBUS3)") (class "Default")
      (node (ref "SJ2") (pin "2") (pinfunction "2_2") (pintype "passive"))
      (node (ref "U3") (pin "16") (pinfunction "CBUS3_16") (pintype "bidirectional"))
    )
    (net (code "47") (name "Net-(U3-DM)") (class "Default")
      (node (ref "R25") (pin "2") (pinfunction "2_2") (pintype "passive"))
      (node (ref "U3") (pin "9") (pinfunction "DM_9") (pintype "bidirectional"))
    )
    (net (code "48") (name "Net-(U3-DP)") (class "Default")
      (node (ref "R26") (pin "2") (pinfunction "2_2") (pintype "passive"))
      (node (ref "U3") (pin "8") (pinfunction "DP_8") (pintype "bidirectional"))
    )
    (net (code "49") (name "Net-(U4-DM0)") (class "Default")
      (node (ref "C12") (pin "1") (pinfunction "1_1") (pintype "passive"))
      (node (ref "R7") (pin "1") (pinfunction "1_1") (pintype "passive"))
      (node (ref "U4") (pin "2") (pinfunction "DM0_2") (pintype "bidirectional"))
      (node (ref "U5") (pin "8") (pinfunction "A_8") (pintype "bidirectional"))
    )
    (net (code "50") (name "Net-(U4-DP0)") (class "Default")
      (node (ref "C11") (pin "1") (pinfunction "1_1") (pintype "passive"))
      (node (ref "R3") (pin "1") (pinfunction "1_1") (pintype "passive"))
      (node (ref "R4") (pin "1") (pinfunction "1_1") (pintype "passive"))
      (node (ref "U4") (pin "1") (pinfunction "DP0_1") (pintype "bidirectional"))
      (node (ref "U5") (pin "6") (pinfunction "B_6") (pintype "bidirectional"))
    )
    (net (code "51") (name "Net-(U4-XTAL1)") (class "Default")
      (node (ref "C32") (pin "1") (pinfunction "1_1") (pintype "passive"))
      (node (ref "U4") (pin "30") (pinfunction "XTAL1_30") (pintype "bidirectional"))
      (node (ref "Y1") (pin "1") (pinfunction "1_1") (pintype "passive"))
    )
    (net (code "52") (name "Net-(U4-XTAL2)") (class "Default")
      (node (ref "R37") (pin "1") (pinfunction "1_1") (pintype "passive"))
      (node (ref "U4") (pin "29") (pinfunction "XTAL2_29") (pintype "bidirectional"))
    )
    (net (code "53") (name "Net-(U4-~{EXTMEM})") (class "Default")
      (node (ref "SJ5") (pin "2") (pinfunction "2_2") (pintype "passive"))
      (node (ref "U4") (pin "26") (pinfunction "~{EXTMEM}_26") (pintype "bidirectional"))
    )
    (net (code "54") (name "Net-(U4-~{OVRCUR1})") (class "Default")
      (node (ref "R28") (pin "2") (pinfunction "2_2") (pintype "passive"))
      (node (ref "U4") (pin "10") (pinfunction "~{OVRCUR1}_10") (pintype "bidirectional"))
      (node (ref "U4") (pin "14") (pinfunction "~{OVRCUR2}_14") (pintype "bidirectional"))
      (node (ref "U4") (pin "18") (pinfunction "~{OVRCUR3}_18") (pintype "bidirectional"))
      (node (ref "U4") (pin "22") (pinfunction "~{OVRCUR4}_22") (pintype "bidirectional"))
      (node (ref "U7") (pin "5") (pinfunction "~{OC}_5") (pintype "bidirectional"))
    )
    (net (code "55") (name "Net-(U4-~{PWRON1})") (class "Default")
      (node (ref "R8") (pin "2") (pinfunction "2_2") (pintype "passive"))
      (node (ref "U4") (pin "13") (pinfunction "~{PWRON2}_13") (pintype "bidirectional"))
      (node (ref "U4") (pin "17") (pinfunction "~{PWRON3}_17") (pintype "bidirectional"))
      (node (ref "U4") (pin "21") (pinfunction "~{PWRON4}_21") (pintype "bidirectional"))
      (node (ref "U4") (pin "9") (pinfunction "~{PWRON1}_9") (pintype "bidirectional"))
      (node (ref "U7") (pin "4") (pinfunction "~{EN}_4") (pintype "bidirectional"))
    )
    (net (code "56") (name "Net-(U4-~{RESET})") (class "Default")
      (node (ref "C7") (pin "1") (pinfunction "1_1") (pintype "passive"))
      (node (ref "R9") (pin "2") (pinfunction "2_2") (pintype "passive"))
      (node (ref "U4") (pin "4") (pinfunction "~{RESET}_4") (pintype "bidirectional"))
    )
    (net (code "57") (name "Net-(U6-R)") (class "Default")
      (node (ref "RN3") (pin "1") (pinfunction "1_1") (pintype "passive"))
      (node (ref "RX3") (pin "C") (pinfunction "C_C") (pintype "passive"))
      (node (ref "U6") (pin "1") (pinfunction "R_1") (pintype "bidirectional"))
      (node (ref "U8") (pin "4") (pinfunction "RXD_4") (pintype "bidirectional"))
    )
    (net (code "58") (name "Net-(U8-CBUS3)") (class "Default")
      (node (ref "SJ3") (pin "2") (pinfunction "2_2") (pintype "passive"))
      (node (ref "U8") (pin "16") (pinfunction "CBUS3_16") (pintype "bidirectional"))
    )
    (net (code "59") (name "Net-(U8-DM)") (class "Default")
      (node (ref "R30") (pin "2") (pinfunction "2_2") (pintype "passive"))
      (node (ref "U8") (pin "9") (pinfunction "DM_9") (pintype "bidirectional"))
    )
    (net (code "60") (name "Net-(U8-DP)") (class "Default")
      (node (ref "R31") (pin "2") (pinfunction "2_2") (pintype "passive"))
      (node (ref "U8") (pin "8") (pinfunction "DP_8") (pintype "bidirectional"))
    )
    (net (code "61") (name "Net-(U9-BP)") (class "Default")
      (node (ref "C4") (pin "1") (pinfunction "1_1") (pintype "passive"))
      (node (ref "U9") (pin "4") (pinfunction "BP_4") (pintype "input"))
    )
    (net (code "62") (name "Net-(U11-3V3-OUT)") (class "Default")
      (node (ref "C30") (pin "1") (pinfunction "1_1") (pintype "passive"))
      (node (ref "R33") (pin "2") (pinfunction "2_2") (pintype "passive"))
      (node (ref "R34") (pin "2") (pinfunction "2_2") (pintype "passive"))
      (node (ref "U11") (pin "10") (pinfunction "3V3-OUT_10") (pintype "bidirectional"))
      (node (ref "U11") (pin "11") (pinfunction "RESET_11") (pintype "bidirectional"))
      (node (ref "U11") (pin "3") (pinfunction "VCCO_3") (pintype "bidirectional"))
    )
    (net (code "63") (name "Net-(U11-CBUS1)") (class "Default")
      (node (ref "RX4") (pin "C") (pinfunction "C_C") (pintype "passive"))
      (node (ref "U11") (pin "14") (pinfunction "CBUS1_14") (pintype "bidirectional"))
    )
    (net (code "64") (name "Net-(U11-CBUS2)") (class "Default")
      (node (ref "TX4") (pin "C") (pinfunction "C_C") (pintype "passive"))
      (node (ref "U11") (pin "7") (pinfunction "CBUS2_7") (pintype "bidirectional"))
    )
    (net (code "65") (name "Net-(U11-CBUS3)") (class "Default")
      (node (ref "SJ4") (pin "2") (pinfunction "2_2") (pintype "passive"))
      (node (ref "U11") (pin "16") (pinfunction "CBUS3_16") (pintype "bidirectional"))
    )
    (net (code "66") (name "Net-(U11-DM)") (class "Default")
      (node (ref "R35") (pin "2") (pinfunction "2_2") (pintype "passive"))
      (node (ref "U11") (pin "9") (pinfunction "DM_9") (pintype "bidirectional"))
    )
    (net (code "67") (name "Net-(U11-DP)") (class "Default")
      (node (ref "R36") (pin "2") (pinfunction "2_2") (pintype "passive"))
      (node (ref "U11") (pin "8") (pinfunction "DP_8") (pintype "bidirectional"))
    )
    (net (code "68") (name "Net-(U11-RXD)") (class "Default")
      (node (ref "J2") (pin "9") (pinfunction "9_9") (pintype "passive"))
      (node (ref "U11") (pin "4") (pinfunction "RXD_4") (pintype "bidirectional"))
    )
    (net (code "69") (name "Net-(U11-TXD)") (class "Default")
      (node (ref "J2") (pin "10") (pinfunction "10_10") (pintype "passive"))
      (node (ref "U11") (pin "1") (pinfunction "TXD_1") (pintype "bidirectional"))
    )
    (net (code "70") (name "Net-(U19-R)") (class "Default")
      (node (ref "RN1") (pin "1") (pinfunction "1_1") (pintype "passive"))
      (node (ref "RX1") (pin "C") (pinfunction "C_C") (pintype "passive"))
      (node (ref "U19") (pin "1") (pinfunction "R_1") (pintype "bidirectional"))
      (node (ref "U2") (pin "4") (pinfunction "RXD_4") (pintype "bidirectional"))
    )
    (net (code "71") (name "RS485-1-A") (class "Default")
      (node (ref "J2") (pin "15") (pinfunction "15_15") (pintype "passive"))
      (node (ref "U19") (pin "6") (pinfunction "A_6") (pintype "bidirectional"))
    )
    (net (code "72") (name "RS485-1-B") (class "Default")
      (node (ref "J2") (pin "16") (pinfunction "16_16") (pintype "passive"))
      (node (ref "U19") (pin "7") (pinfunction "B_7") (pintype "bidirectional"))
    )
    (net (code "73") (name "RS485-2-A") (class "Default")
      (node (ref "J2") (pin "13") (pinfunction "13_13") (pintype "passive"))
      (node (ref "U1") (pin "6") (pinfunction "A_6") (pintype "bidirectional"))
    )
    (net (code "74") (name "RS485-2-B") (class "Default")
      (node (ref "J2") (pin "14") (pinfunction "14_14") (pintype "passive"))
      (node (ref "U1") (pin "7") (pinfunction "B_7") (pintype "bidirectional"))
    )
    (net (code "75") (name "RS485-3-A") (class "Default")
      (node (ref "J2") (pin "11") (pinfunction "11_11") (pintype "passive"))
      (node (ref "U6") (pin "6") (pinfunction "A_6") (pintype "bidirectional"))
    )
    (net (code "76") (name "RS485-3-B") (class "Default")
      (node (ref "J2") (pin "12") (pinfunction "12_12") (pintype "passive"))
      (node (ref "U6") (pin "7") (pinfunction "B_7") (pintype "bidirectional"))
    )
    (net (code "77") (name "VCC") (class "Default")
      (node (ref "C2") (pin "1") (pinfunction "1_1") (pintype "passive"))
      (node (ref "C22") (pin "1") (pinfunction "1_1") (pintype "passive"))
      (node (ref "C23") (pin "1") (pinfunction "1_1") (pintype "passive"))
      (node (ref "C28") (pin "1") (pinfunction "1_1") (pintype "passive"))
      (node (ref "C29") (pin "1") (pinfunction "1_1") (pintype "passive"))
      (node (ref "C3") (pin "1") (pinfunction "1_1") (pintype "passive"))
      (node (ref "C5") (pin "1") (pinfunction "1_1") (pintype "passive"))
      (node (ref "JP1") (pin "1") (pinfunction "1_1") (pintype "passive"))
      (node (ref "JP2") (pin "1") (pinfunction "1_1") (pintype "passive"))
      (node (ref "JP3") (pin "1") (pinfunction "1_1") (pintype "passive"))
      (node (ref "JP4") (pin "1") (pinfunction "1_1") (pintype "passive"))
      (node (ref "U1") (pin "8") (pinfunction "VCC_8") (pintype "bidirectional"))
      (node (ref "U11") (pin "12") (pinfunction "VCC_12") (pintype "bidirectional"))
      (node (ref "U19") (pin "8") (pinfunction "VCC_8") (pintype "bidirectional"))
      (node (ref "U2") (pin "12") (pinfunction "VCC_12") (pintype "bidirectional"))
      (node (ref "U3") (pin "12") (pinfunction "VCC_12") (pintype "bidirectional"))
      (node (ref "U6") (pin "8") (pinfunction "VCC_8") (pintype "bidirectional"))
      (node (ref "U7") (pin "6") (pinfunction "OUT_6") (pintype "bidirectional"))
      (node (ref "U7") (pin "7") (pinfunction "OUT_7") (pintype "bidirectional"))
      (node (ref "U7") (pin "8") (pinfunction "OUT_8") (pintype "bidirectional"))
      (node (ref "U8") (pin "12") (pinfunction "VCC_12") (pintype "bidirectional"))
    )
    (net (code "78") (name "unconnected-(J2-Pad1)") (class "Default")
      (node (ref "J2") (pin "1") (pinfunction "1_1") (pintype "passive"))
    )
    (net (code "79") (name "unconnected-(J2-Pad2)") (class "Default")
      (node (ref "J2") (pin "2") (pinfunction "2_2") (pintype "passive"))
    )
    (net (code "80") (name "unconnected-(J2-Pad3)") (class "Default")
      (node (ref "J2") (pin "3") (pinfunction "3_3") (pintype "passive"))
    )
    (net (code "81") (name "unconnected-(J2-Pad4)") (class "Default")
      (node (ref "J2") (pin "4") (pinfunction "4_4") (pintype "passive"))
    )
    (net (code "82") (name "unconnected-(J2-Pad5)") (class "Default")
      (node (ref "J2") (pin "5") (pinfunction "5_5") (pintype "passive"))
    )
    (net (code "83") (name "unconnected-(U2-CBUS1-Pad14)") (class "Default")
      (node (ref "U2") (pin "14") (pinfunction "CBUS1_14") (pintype "bidirectional"))
    )
    (net (code "84") (name "unconnected-(U3-CBUS1-Pad14)") (class "Default")
      (node (ref "U3") (pin "14") (pinfunction "CBUS1_14") (pintype "bidirectional"))
    )
    (net (code "85") (name "unconnected-(U4-EECLK-Pad5)") (class "Default")
      (node (ref "U4") (pin "5") (pinfunction "EECLK_5") (pintype "bidirectional"))
    )
    (net (code "86") (name "unconnected-(U4-SUSPND-Pad32)") (class "Default")
      (node (ref "U4") (pin "32") (pinfunction "SUSPND_32") (pintype "bidirectional"))
    )
    (net (code "87") (name "unconnected-(U5-C-Pad2)") (class "Default")
      (node (ref "U5") (pin "2") (pinfunction "C_2") (pintype "bidirectional"))
    )
    (net (code "88") (name "unconnected-(U5-D-Pad4)") (class "Default")
      (node (ref "U5") (pin "4") (pinfunction "D_4") (pintype "bidirectional"))
    )
    (net (code "89") (name "unconnected-(U8-CBUS1-Pad14)") (class "Default")
      (node (ref "U8") (pin "14") (pinfunction "CBUS1_14") (pintype "bidirectional"))
    )
    (net (code "90") (name "unconnected-(U11-CBUS0-Pad15)") (class "Default")
      (node (ref "U11") (pin "15") (pinfunction "CBUS0_15") (pintype "bidirectional"))
    )
  )
)
